# writelockswitches.net
KiCad netlist of a schematic drawn in EAGLE
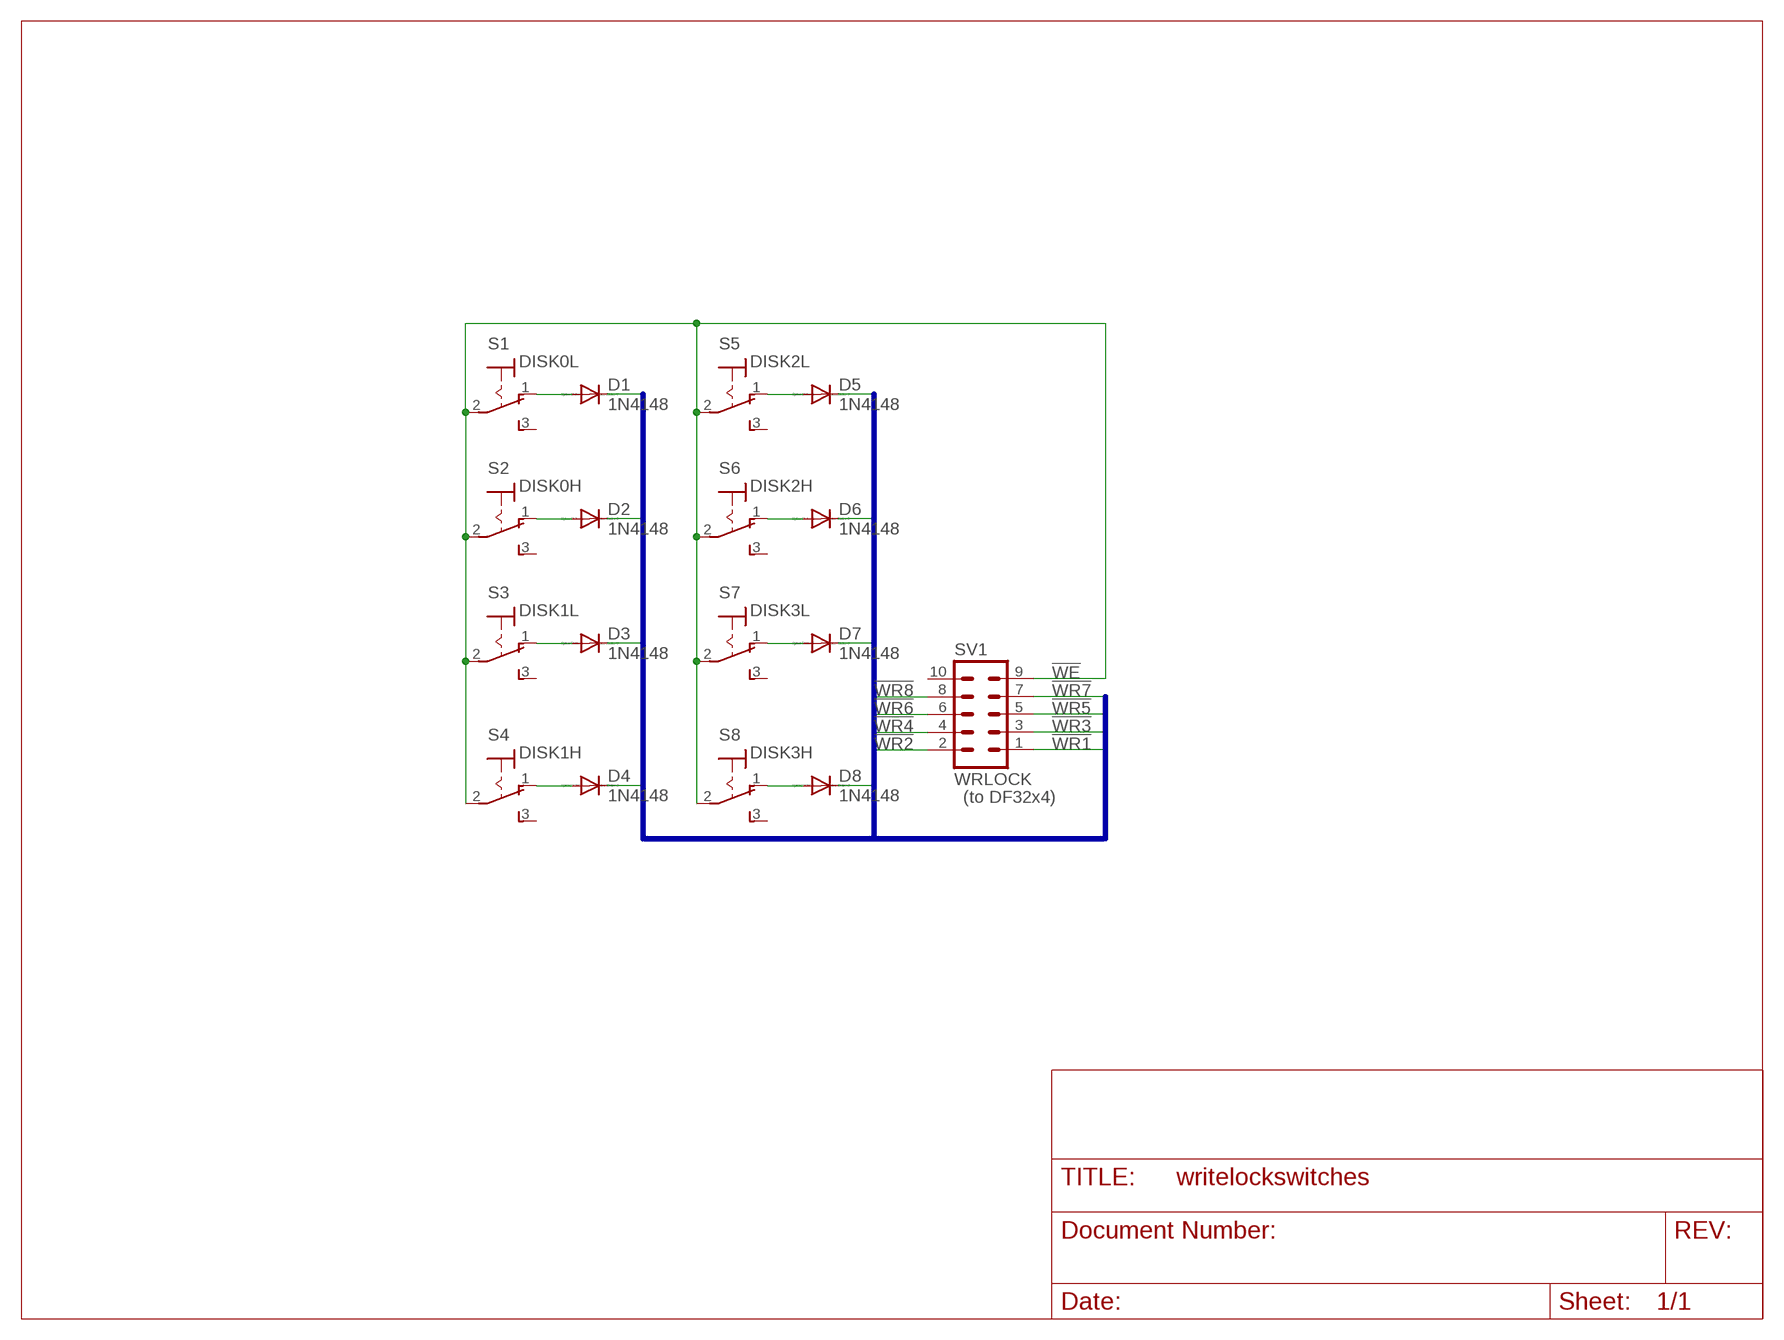
[diagram p0: schematic, sheet 1]

(export (version "E")
  (design (tool "Eeschema 10.0.6"))
  (components
    (comp (ref "D1")
      (value "1N4148")
      (footprint "eagle-import:DO35-10")
      (libsource (lib "eagle-import") (part "1N4148DO35-10"))
    )
    (comp (ref "D2")
      (value "1N4148")
      (footprint "eagle-import:DO35-10")
      (libsource (lib "eagle-import") (part "1N4148DO35-10"))
    )
    (comp (ref "D3")
      (value "1N4148")
      (footprint "eagle-import:DO35-10")
      (libsource (lib "eagle-import") (part "1N4148DO35-10"))
    )
    (comp (ref "D4")
      (value "1N4148")
      (footprint "eagle-import:DO35-10")
      (libsource (lib "eagle-import") (part "1N4148DO35-10"))
    )
    (comp (ref "D5")
      (value "1N4148")
      (footprint "eagle-import:DO35-10")
      (libsource (lib "eagle-import") (part "1N4148DO35-10"))
    )
    (comp (ref "D6")
      (value "1N4148")
      (footprint "eagle-import:DO35-10")
      (libsource (lib "eagle-import") (part "1N4148DO35-10"))
    )
    (comp (ref "D7")
      (value "1N4148")
      (footprint "eagle-import:DO35-10")
      (libsource (lib "eagle-import") (part "1N4148DO35-10"))
    )
    (comp (ref "D8")
      (value "1N4148")
      (footprint "eagle-import:DO35-10")
      (libsource (lib "eagle-import") (part "1N4148DO35-10"))
    )
    (comp (ref "S1")
      (value "DISK0L")
      (footprint "eagle-import:320-916")
      (libsource (lib "eagle-import") (part "320-916"))
    )
    (comp (ref "S2")
      (value "DISK0H")
      (footprint "eagle-import:320-916")
      (libsource (lib "eagle-import") (part "320-916"))
    )
    (comp (ref "S3")
      (value "DISK1L")
      (footprint "eagle-import:320-916")
      (libsource (lib "eagle-import") (part "320-916"))
    )
    (comp (ref "S4")
      (value "DISK1H")
      (footprint "eagle-import:320-916")
      (libsource (lib "eagle-import") (part "320-916"))
    )
    (comp (ref "S5")
      (value "DISK2L")
      (footprint "eagle-import:320-916")
      (libsource (lib "eagle-import") (part "320-916"))
    )
    (comp (ref "S6")
      (value "DISK2H")
      (footprint "eagle-import:320-916")
      (libsource (lib "eagle-import") (part "320-916"))
    )
    (comp (ref "S7")
      (value "DISK3L")
      (footprint "eagle-import:320-916")
      (libsource (lib "eagle-import") (part "320-916"))
    )
    (comp (ref "S8")
      (value "DISK3H")
      (footprint "eagle-import:320-916")
      (libsource (lib "eagle-import") (part "320-916"))
    )
    (comp (ref "SV1")
      (value "WRLOCK")
      (footprint "eagle-import:MA05-2")
      (libsource (lib "eagle-import") (part "MA05-2"))
    )
  )
  (nets
    (net (code "1") (name "/~{WE}") (class "Default")
      (node (ref "S1") (pin "2") (pinfunction "P_2") (pintype "passive"))
      (node (ref "S2") (pin "2") (pinfunction "P_2") (pintype "passive"))
      (node (ref "S3") (pin "2") (pinfunction "P_2") (pintype "passive"))
      (node (ref "S4") (pin "2") (pinfunction "P_2") (pintype "passive"))
      (node (ref "S5") (pin "2") (pinfunction "P_2") (pintype "passive"))
      (node (ref "S6") (pin "2") (pinfunction "P_2") (pintype "passive"))
      (node (ref "S7") (pin "2") (pinfunction "P_2") (pintype "passive"))
      (node (ref "S8") (pin "2") (pinfunction "P_2") (pintype "passive"))
      (node (ref "SV1") (pin "9") (pinfunction "9_9") (pintype "passive"))
    )
    (net (code "2") (name "/~{WR1}") (class "Default")
      (node (ref "D1") (pin "C") (pinfunction "C_C") (pintype "passive"))
      (node (ref "SV1") (pin "1") (pinfunction "1_1") (pintype "passive"))
    )
    (net (code "3") (name "/~{WR2}") (class "Default")
      (node (ref "D2") (pin "C") (pinfunction "C_C") (pintype "passive"))
      (node (ref "SV1") (pin "2") (pinfunction "2_2") (pintype "passive"))
    )
    (net (code "4") (name "/~{WR3}") (class "Default")
      (node (ref "D3") (pin "C") (pinfunction "C_C") (pintype "passive"))
      (node (ref "SV1") (pin "3") (pinfunction "3_3") (pintype "passive"))
    )
    (net (code "5") (name "/~{WR4}") (class "Default")
      (node (ref "D4") (pin "C") (pinfunction "C_C") (pintype "passive"))
      (node (ref "SV1") (pin "4") (pinfunction "4_4") (pintype "passive"))
    )
    (net (code "6") (name "/~{WR5}") (class "Default")
      (node (ref "D5") (pin "C") (pinfunction "C_C") (pintype "passive"))
      (node (ref "SV1") (pin "5") (pinfunction "5_5") (pintype "passive"))
    )
    (net (code "7") (name "/~{WR6}") (class "Default")
      (node (ref "D6") (pin "C") (pinfunction "C_C") (pintype "passive"))
      (node (ref "SV1") (pin "6") (pinfunction "6_6") (pintype "passive"))
    )
    (net (code "8") (name "/~{WR7}") (class "Default")
      (node (ref "D7") (pin "C") (pinfunction "C_C") (pintype "passive"))
      (node (ref "SV1") (pin "7") (pinfunction "7_7") (pintype "passive"))
    )
    (net (code "9") (name "/~{WR8}") (class "Default")
      (node (ref "D8") (pin "C") (pinfunction "C_C") (pintype "passive"))
      (node (ref "SV1") (pin "8") (pinfunction "8_8") (pintype "passive"))
    )
    (net (code "10") (name "Net-(S1-O)") (class "Default")
      (node (ref "D1") (pin "A") (pinfunction "A_A") (pintype "passive"))
      (node (ref "S1") (pin "1") (pinfunction "O_1") (pintype "passive"))
    )
    (net (code "11") (name "Net-(S2-O)") (class "Default")
      (node (ref "D2") (pin "A") (pinfunction "A_A") (pintype "passive"))
      (node (ref "S2") (pin "1") (pinfunction "O_1") (pintype "passive"))
    )
    (net (code "12") (name "Net-(S3-O)") (class "Default")
      (node (ref "D3") (pin "A") (pinfunction "A_A") (pintype "passive"))
      (node (ref "S3") (pin "1") (pinfunction "O_1") (pintype "passive"))
    )
    (net (code "13") (name "Net-(S4-O)") (class "Default")
      (node (ref "D4") (pin "A") (pinfunction "A_A") (pintype "passive"))
      (node (ref "S4") (pin "1") (pinfunction "O_1") (pintype "passive"))
    )
    (net (code "14") (name "Net-(S5-O)") (class "Default")
      (node (ref "D5") (pin "A") (pinfunction "A_A") (pintype "passive"))
      (node (ref "S5") (pin "1") (pinfunction "O_1") (pintype "passive"))
    )
    (net (code "15") (name "Net-(S6-O)") (class "Default")
      (node (ref "D6") (pin "A") (pinfunction "A_A") (pintype "passive"))
      (node (ref "S6") (pin "1") (pinfunction "O_1") (pintype "passive"))
    )
    (net (code "16") (name "Net-(S7-O)") (class "Default")
      (node (ref "D7") (pin "A") (pinfunction "A_A") (pintype "passive"))
      (node (ref "S7") (pin "1") (pinfunction "O_1") (pintype "passive"))
    )
    (net (code "17") (name "Net-(S8-O)") (class "Default")
      (node (ref "D8") (pin "A") (pinfunction "A_A") (pintype "passive"))
      (node (ref "S8") (pin "1") (pinfunction "O_1") (pintype "passive"))
    )
    (net (code "18") (name "unconnected-(S1-S-Pad3)") (class "Default")
      (node (ref "S1") (pin "3") (pinfunction "S_3") (pintype "passive"))
    )
    (net (code "19") (name "unconnected-(S2-S-Pad3)") (class "Default")
      (node (ref "S2") (pin "3") (pinfunction "S_3") (pintype "passive"))
    )
    (net (code "20") (name "unconnected-(S3-S-Pad3)") (class "Default")
      (node (ref "S3") (pin "3") (pinfunction "S_3") (pintype "passive"))
    )
    (net (code "21") (name "unconnected-(S4-S-Pad3)") (class "Default")
      (node (ref "S4") (pin "3") (pinfunction "S_3") (pintype "passive"))
    )
    (net (code "22") (name "unconnected-(S5-S-Pad3)") (class "Default")
      (node (ref "S5") (pin "3") (pinfunction "S_3") (pintype "passive"))
    )
    (net (code "23") (name "unconnected-(S6-S-Pad3)") (class "Default")
      (node (ref "S6") (pin "3") (pinfunction "S_3") (pintype "passive"))
    )
    (net (code "24") (name "unconnected-(S7-S-Pad3)") (class "Default")
      (node (ref "S7") (pin "3") (pinfunction "S_3") (pintype "passive"))
    )
    (net (code "25") (name "unconnected-(S8-S-Pad3)") (class "Default")
      (node (ref "S8") (pin "3") (pinfunction "S_3") (pintype "passive"))
    )
    (net (code "26") (name "unconnected-(SV1-Pad10)") (class "Default")
      (node (ref "SV1") (pin "10") (pinfunction "10_10") (pintype "passive"))
    )
  )
)
